# ANA_FE.net
KiCad netlist of a schematic drawn in Altium Designer
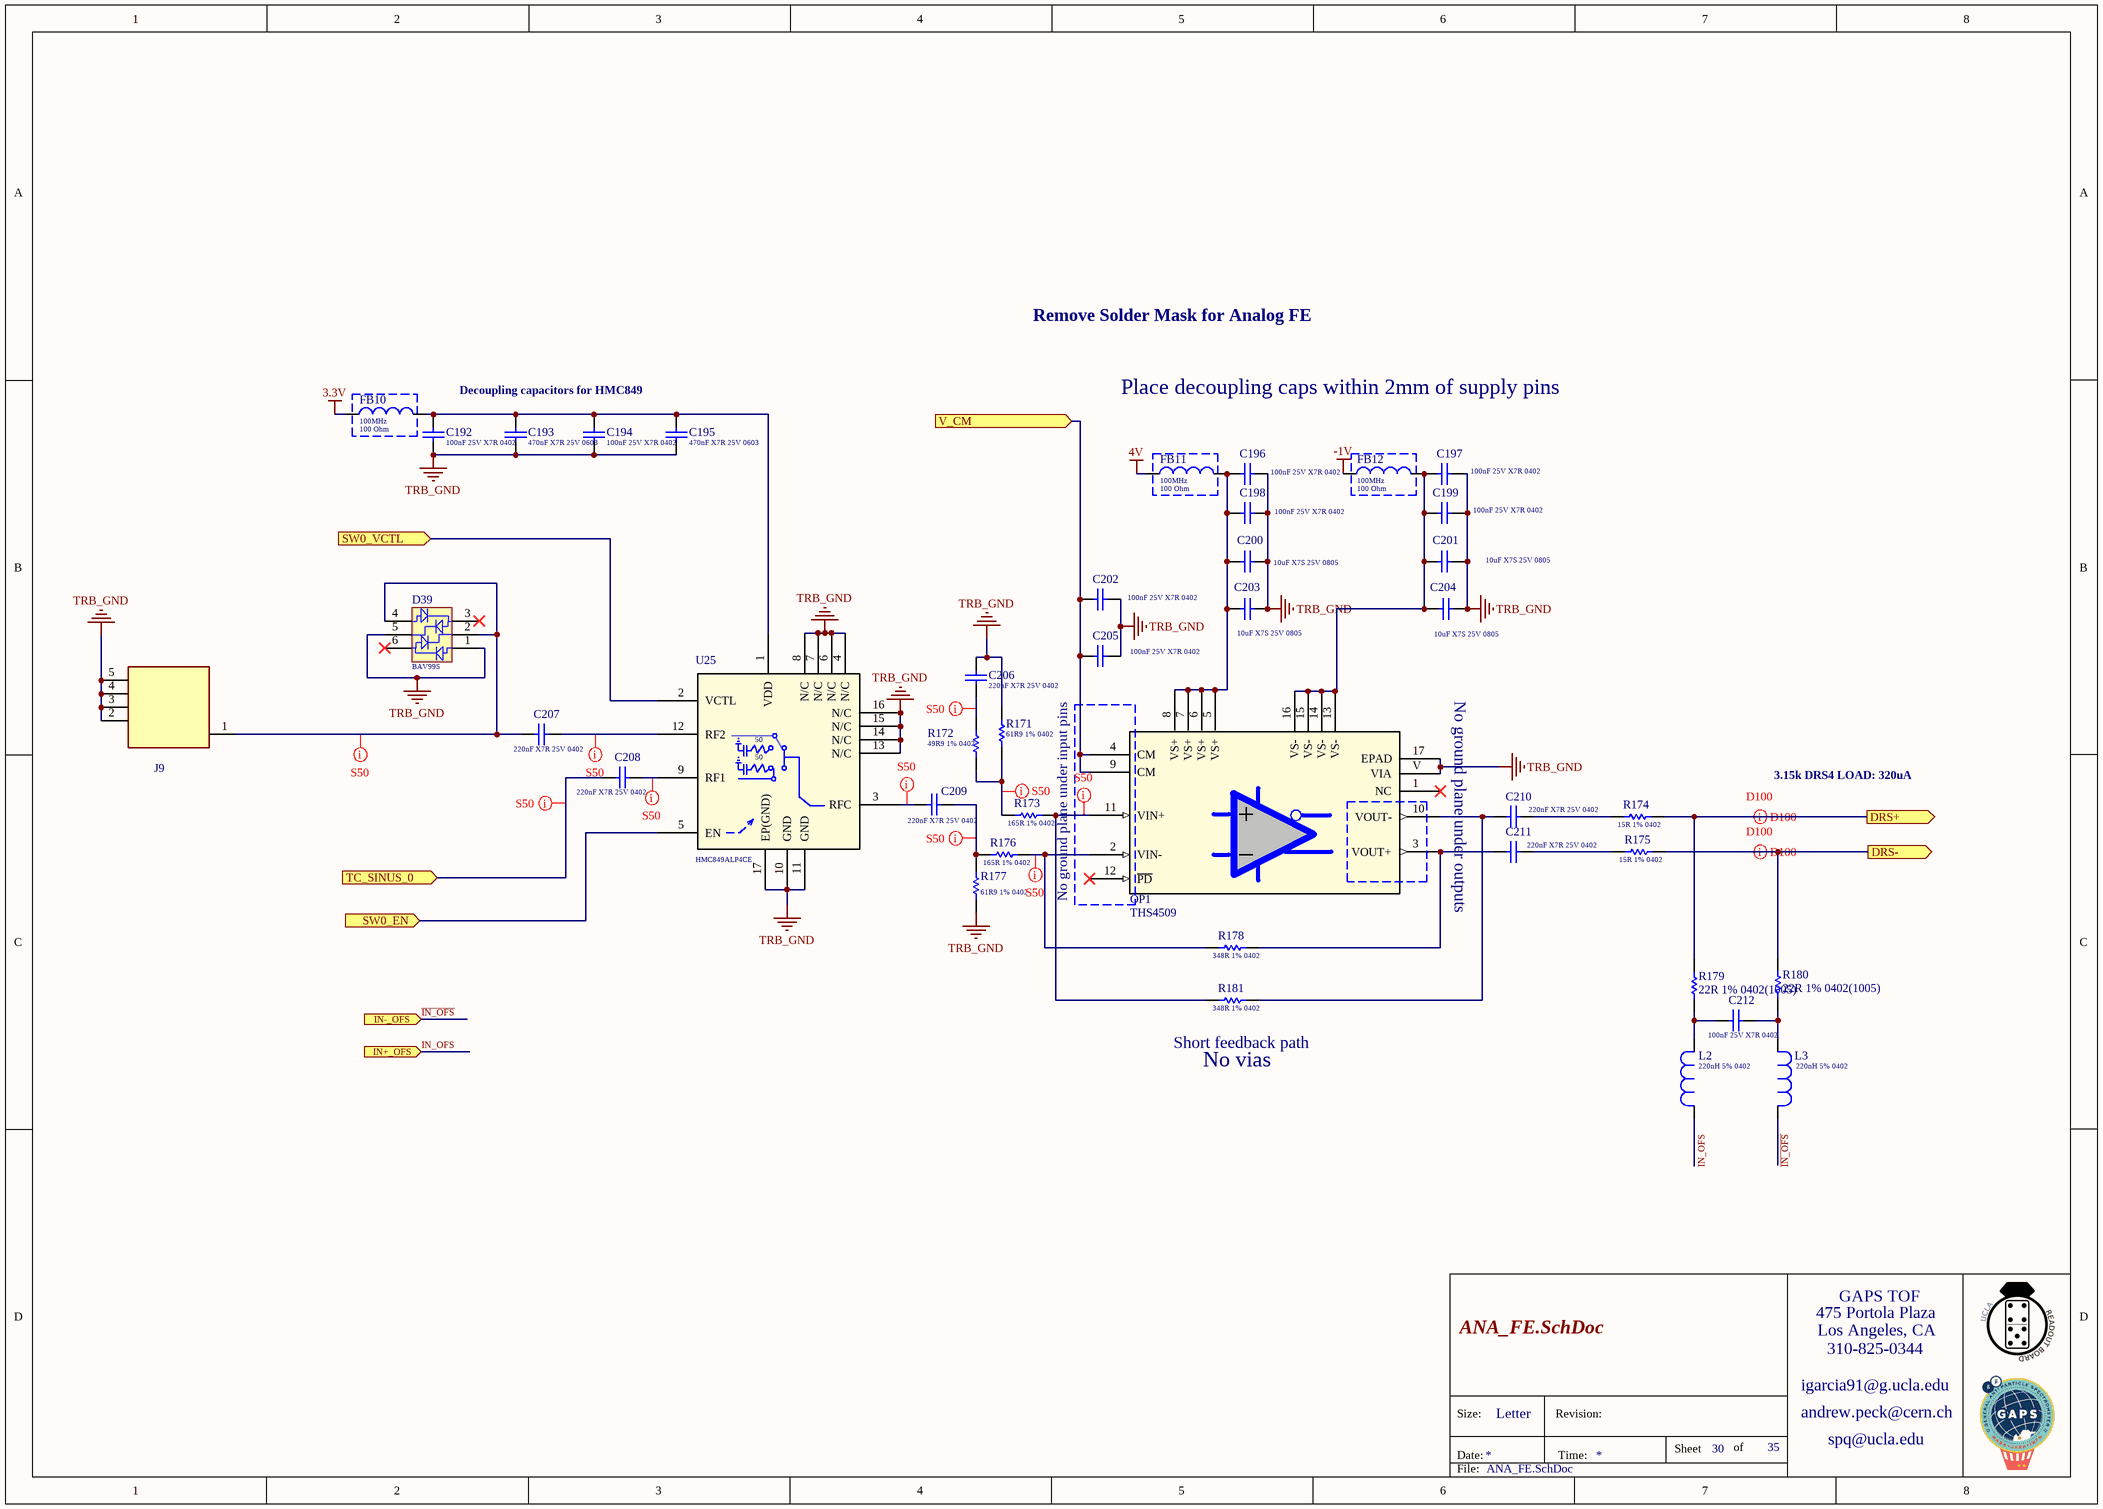
[diagram p0: ANA_FE.SchDoc]

(export (version "E")
  (design (tool "Eeschema 10.0.6"))
  (components
    (comp (ref "C192")
      (value "Cap_Taiyo_Yuden_TMK105B7104KV-FR_100nF")
      (footprint "Cap_Taiyo_Yuden_TMK105B7104KV-FR_100nF")
      (description "CAP CER 100nF 25V X7R 0402")
      (fields (field (name "CAPACITANCE") "100nF 25V X7R 0402"))
      (libsource (lib "Cap_Taiyo_Yuden_TMK105B7104KV-FR_100nF") (part "Cap_Taiyo_Yuden_TMK105B7104KV-FR_100nF"))
    )
    (comp (ref "C193")
      (value "Cap_Wurth_Electronics_885012206075_470nF")
      (footprint "Cap_Wurth_Electronics_885012206075_470nF")
      (description "CAP CER 470nF 25V X7R 0603")
      (fields (field (name "CAPACITANCE") "470nF X7R 25V 0603"))
      (libsource (lib "Cap_Wurth_Electronics_885012206075_470nF") (part "Cap_Wurth_Electronics_885012206075_470nF"))
    )
    (comp (ref "C194")
      (value "Cap_Taiyo_Yuden_TMK105B7104KV-FR_100nF")
      (footprint "Cap_Taiyo_Yuden_TMK105B7104KV-FR_100nF")
      (description "CAP CER 100nF 25V X7R 0402")
      (fields (field (name "CAPACITANCE") "100nF 25V X7R 0402"))
      (libsource (lib "Cap_Taiyo_Yuden_TMK105B7104KV-FR_100nF") (part "Cap_Taiyo_Yuden_TMK105B7104KV-FR_100nF"))
    )
    (comp (ref "C195")
      (value "Cap_Wurth_Electronics_885012206075_470nF")
      (footprint "Cap_Wurth_Electronics_885012206075_470nF")
      (description "CAP CER 470nF 25V X7R 0603")
      (fields (field (name "CAPACITANCE") "470nF X7R 25V 0603"))
      (libsource (lib "Cap_Wurth_Electronics_885012206075_470nF") (part "Cap_Wurth_Electronics_885012206075_470nF"))
    )
    (comp (ref "C196")
      (value "Cap_Taiyo_Yuden_TMK105B7104KV-FR_100nF")
      (footprint "Cap_Taiyo_Yuden_TMK105B7104KV-FR_100nF")
      (description "CAP CER 100nF 25V X7R 0402")
      (fields (field (name "CAPACITANCE") "100nF 25V X7R 0402"))
      (libsource (lib "Cap_Taiyo_Yuden_TMK105B7104KV-FR_100nF") (part "Cap_Taiyo_Yuden_TMK105B7104KV-FR_100nF"))
    )
    (comp (ref "C197")
      (value "Cap_Taiyo_Yuden_TMK105B7104KV-FR_100nF")
      (footprint "Cap_Taiyo_Yuden_TMK105B7104KV-FR_100nF")
      (description "CAP CER 100nF 25V X7R 0402")
      (fields (field (name "CAPACITANCE") "100nF 25V X7R 0402"))
      (libsource (lib "Cap_Taiyo_Yuden_TMK105B7104KV-FR_100nF") (part "Cap_Taiyo_Yuden_TMK105B7104KV-FR_100nF"))
    )
    (comp (ref "C198")
      (value "Cap_Taiyo_Yuden_TMK105B7104KV-FR_100nF")
      (footprint "Cap_Taiyo_Yuden_TMK105B7104KV-FR_100nF")
      (description "CAP CER 100nF 25V X7R 0402")
      (fields (field (name "CAPACITANCE") "100nF 25V X7R 0402"))
      (libsource (lib "Cap_Taiyo_Yuden_TMK105B7104KV-FR_100nF") (part "Cap_Taiyo_Yuden_TMK105B7104KV-FR_100nF"))
    )
    (comp (ref "C199")
      (value "Cap_Taiyo_Yuden_TMK105B7104KV-FR_100nF")
      (footprint "Cap_Taiyo_Yuden_TMK105B7104KV-FR_100nF")
      (description "CAP CER 100nF 25V X7R 0402")
      (fields (field (name "CAPACITANCE") "100nF 25V X7R 0402"))
      (libsource (lib "Cap_Taiyo_Yuden_TMK105B7104KV-FR_100nF") (part "Cap_Taiyo_Yuden_TMK105B7104KV-FR_100nF"))
    )
    (comp (ref "C200")
      (value "Cap_Murata_ GRM21BC71E106ME11L_10uF")
      (footprint "Cap_Murata_ GRM21BC71E106ME11L_10uF")
      (description "CAP CER 10uF 25V X7R 0805")
      (fields (field (name "CAPACITANCE") "10uF X7S 25V 0805"))
      (libsource (lib "Cap_Murata_ GRM21BC71E106ME11L_10uF") (part "Cap_Murata_ GRM21BC71E106ME11L_10uF"))
    )
    (comp (ref "C201")
      (value "Cap_Murata_ GRM21BC71E106ME11L_10uF")
      (footprint "Cap_Murata_ GRM21BC71E106ME11L_10uF")
      (description "CAP CER 10uF 25V X7R 0805")
      (fields (field (name "CAPACITANCE") "10uF X7S 25V 0805"))
      (libsource (lib "Cap_Murata_ GRM21BC71E106ME11L_10uF") (part "Cap_Murata_ GRM21BC71E106ME11L_10uF"))
    )
    (comp (ref "C202")
      (value "Cap_Taiyo_Yuden_TMK105B7104KV-FR_100nF")
      (footprint "Cap_Taiyo_Yuden_TMK105B7104KV-FR_100nF")
      (description "CAP CER 100nF 25V X7R 0402")
      (fields (field (name "CAPACITANCE") "100nF 25V X7R 0402"))
      (libsource (lib "Cap_Taiyo_Yuden_TMK105B7104KV-FR_100nF") (part "Cap_Taiyo_Yuden_TMK105B7104KV-FR_100nF"))
    )
    (comp (ref "C203")
      (value "Cap_Murata_ GRM21BC71E106ME11L_10uF")
      (footprint "Cap_Murata_ GRM21BC71E106ME11L_10uF")
      (description "CAP CER 10uF 25V X7R 0805")
      (fields (field (name "CAPACITANCE") "10uF X7S 25V 0805"))
      (libsource (lib "Cap_Murata_ GRM21BC71E106ME11L_10uF") (part "Cap_Murata_ GRM21BC71E106ME11L_10uF"))
    )
    (comp (ref "C204")
      (value "Cap_Murata_ GRM21BC71E106ME11L_10uF")
      (footprint "Cap_Murata_ GRM21BC71E106ME11L_10uF")
      (description "CAP CER 10uF 25V X7R 0805")
      (fields (field (name "CAPACITANCE") "10uF X7S 25V 0805"))
      (libsource (lib "Cap_Murata_ GRM21BC71E106ME11L_10uF") (part "Cap_Murata_ GRM21BC71E106ME11L_10uF"))
    )
    (comp (ref "C205")
      (value "Cap_Taiyo_Yuden_TMK105B7104KV-FR_100nF")
      (footprint "Cap_Taiyo_Yuden_TMK105B7104KV-FR_100nF")
      (description "CAP CER 100nF 25V X7R 0402")
      (fields (field (name "CAPACITANCE") "100nF 25V X7R 0402"))
      (libsource (lib "Cap_Taiyo_Yuden_TMK105B7104KV-FR_100nF") (part "Cap_Taiyo_Yuden_TMK105B7104KV-FR_100nF"))
    )
    (comp (ref "C206")
      (value "Cap_TDK_C1608X5R1A106M080AC_220nF")
      (footprint "Cap_TDK_C1608X5R1A106M080AC_220nF")
      (description "CAP CER 220nF 50V X7R 0402")
      (fields (field (name "CAPACITANCE") "220nF X7R 25V 0402"))
      (libsource (lib "Cap_TDK_C1608X5R1A106M080AC_220nF") (part "Cap_TDK_C1608X5R1A106M080AC_220nF"))
    )
    (comp (ref "C207")
      (value "Cap_TDK_C1608X5R1A106M080AC_220nF")
      (footprint "Cap_TDK_C1608X5R1A106M080AC_220nF")
      (description "CAP CER 220nF 50V X7R 0402")
      (fields (field (name "CAPACITANCE") "220nF X7R 25V 0402"))
      (libsource (lib "Cap_TDK_C1608X5R1A106M080AC_220nF") (part "Cap_TDK_C1608X5R1A106M080AC_220nF"))
    )
    (comp (ref "C208")
      (value "Cap_TDK_C1608X5R1A106M080AC_220nF")
      (footprint "Cap_TDK_C1608X5R1A106M080AC_220nF")
      (description "CAP CER 220nF 50V X7R 0402")
      (fields (field (name "CAPACITANCE") "220nF X7R 25V 0402"))
      (libsource (lib "Cap_TDK_C1608X5R1A106M080AC_220nF") (part "Cap_TDK_C1608X5R1A106M080AC_220nF"))
    )
    (comp (ref "C209")
      (value "Cap_TDK_C1608X5R1A106M080AC_220nF")
      (footprint "Cap_TDK_C1608X5R1A106M080AC_220nF")
      (description "CAP CER 220nF 50V X7R 0402")
      (fields (field (name "CAPACITANCE") "220nF X7R 25V 0402"))
      (libsource (lib "Cap_TDK_C1608X5R1A106M080AC_220nF") (part "Cap_TDK_C1608X5R1A106M080AC_220nF"))
    )
    (comp (ref "C210")
      (value "Cap_TDK_C1608X5R1A106M080AC_220nF")
      (footprint "Cap_TDK_C1608X5R1A106M080AC_220nF")
      (description "CAP CER 220nF 50V X7R 0402")
      (fields (field (name "CAPACITANCE") "220nF X7R 25V 0402"))
      (libsource (lib "Cap_TDK_C1608X5R1A106M080AC_220nF") (part "Cap_TDK_C1608X5R1A106M080AC_220nF"))
    )
    (comp (ref "C211")
      (value "Cap_TDK_C1608X5R1A106M080AC_220nF")
      (footprint "Cap_TDK_C1608X5R1A106M080AC_220nF")
      (description "CAP CER 220nF 50V X7R 0402")
      (fields (field (name "CAPACITANCE") "220nF X7R 25V 0402"))
      (libsource (lib "Cap_TDK_C1608X5R1A106M080AC_220nF") (part "Cap_TDK_C1608X5R1A106M080AC_220nF"))
    )
    (comp (ref "C212")
      (value "Cap_Taiyo_Yuden_TMK105B7104KV-FR_100nF")
      (footprint "Cap_Taiyo_Yuden_TMK105B7104KV-FR_100nF")
      (description "CAP CER 100nF 25V X7R 0402")
      (fields (field (name "CAPACITANCE") "100nF 25V X7R 0402"))
      (libsource (lib "Cap_Taiyo_Yuden_TMK105B7104KV-FR_100nF") (part "Cap_Taiyo_Yuden_TMK105B7104KV-FR_100nF"))
    )
    (comp (ref "D39")
      (value "BAV99S")
      (footprint "INF-SOT363_V")
      (description "Silicon Switching Diode, SOT363, Reel, Green")
      (fields (field (name "MANUFACTURER") "Infineon"))
      (libsource (lib "Altium Content Vault") (part "INF-D_A1K2C3A4K5C6-6"))
    )
    (comp (ref "FB10")
      (value "742792731")
      (footprint "FB_Wurth_Electronics_742792731_100Ohms")
      (description "FB SMD 100 OHM 25% 1.2A 0402")
      (fields (field (name "MEASURING FREQUENCY") "100MHz") (field (name "IMPEDANCE") "100 Ohm"))
      (libsource (lib "FB_Wurth_Electronics_742792731_100Ohms") (part "FB_Wurth_Electronics_742792731_100Ohms"))
    )
    (comp (ref "FB11")
      (value "742792731")
      (footprint "FB_Wurth_Electronics_742792731_100Ohms")
      (description "FB SMD 100 OHM 25% 1.2A 0402")
      (fields (field (name "MEASURING FREQUENCY") "100MHz") (field (name "IMPEDANCE") "100 Ohm"))
      (libsource (lib "FB_Wurth_Electronics_742792731_100Ohms") (part "FB_Wurth_Electronics_742792731_100Ohms"))
    )
    (comp (ref "FB12")
      (value "742792731")
      (footprint "FB_Wurth_Electronics_742792731_100Ohms")
      (description "FB SMD 100 OHM 25% 1.2A 0402")
      (fields (field (name "MEASURING FREQUENCY") "100MHz") (field (name "IMPEDANCE") "100 Ohm"))
      (libsource (lib "FB_Wurth_Electronics_742792731_100Ohms") (part "FB_Wurth_Electronics_742792731_100Ohms"))
    )
    (comp (ref "J9")
      (value "SMA JACK 50 OHM")
      (footprint "Amphenol_132289_0")
      (description "CONN SMA JACK 50 OHM EDGE MNT")
      (fields (field (name "MANUFACTURER") "Amphenol") (field (name "MOUSER PART NUMBER") "523-132289"))
      (libsource (lib "Conn_Amphenol_132289_eec") (part "Conn_Amphenol_132289_eec"))
    )
    (comp (ref "L2")
      (value "Ind_TDK_ MLG1005SR22JT000_220nH")
      (footprint "Ind_TDK_ MLG1005SR22JT000_220nH")
      (description "Fixed Inductors .22 UH 5%")
      (fields (field (name "INDUCTANCE") "220nH 5% 0402"))
      (libsource (lib "Ind_TDK_ MLG1005SR22JT000_220nH") (part "Ind_TDK_ MLG1005SR22JT000_220nH"))
    )
    (comp (ref "L3")
      (value "Ind_TDK_ MLG1005SR22JT000_220nH")
      (footprint "Ind_TDK_ MLG1005SR22JT000_220nH")
      (description "Fixed Inductors .22 UH 5%")
      (fields (field (name "INDUCTANCE") "220nH 5% 0402"))
      (libsource (lib "Ind_TDK_ MLG1005SR22JT000_220nH") (part "Ind_TDK_ MLG1005SR22JT000_220nH"))
    )
    (comp (ref "OP1")
      (value "THS4509")
      (footprint "RGT16")
      (description "Differential Amplifier 1 Circuit Differential 16-QFN (3x3)")
      (fields (field (name "MANUFACTURER_PART_NUMBER") "THS4509RGTT"))
      (libsource (lib "THS4509RGTT") (part "THS4509RGTT"))
    )
    (comp (ref "R171")
      (value "61R9 1% 0402")
      (footprint "RESC0402(1005)_L")
      (description "61R9 0.063W 1% 0402 (1005 Metric)  SMD")
      (fields (field (name "TOLERANCE") "1 %") (field (name "POWER") "0.063 W"))
      (libsource (lib "Altium Content Vault") (part "RES"))
    )
    (comp (ref "R172")
      (value "49R9 1% 0402")
      (footprint "RESC0402(1005)_L")
      (description "49R9 0.063W 1% 0402 (1005 Metric)  SMD")
      (fields (field (name "POWER") "0.063 W") (field (name "TOLERANCE") "1 %"))
      (libsource (lib "Altium Content Vault") (part "RES"))
    )
    (comp (ref "R173")
      (value "165R 1% 0402")
      (footprint "RESC0402(1005)_L")
      (description "165R 0.063W 1% 0402 (1005 Metric)  SMD")
      (fields (field (name "POWER") "0.063 W") (field (name "TOLERANCE") "1 %"))
      (libsource (lib "Altium Content Vault") (part "RES"))
    )
    (comp (ref "R174")
      (value "15R 1% 0402")
      (footprint "RESC0402(1005)_L")
      (description "15R 0.063W 1% 0402 (1005 Metric)  SMD")
      (fields (field (name "TOLERANCE") "1 %") (field (name "POWER") "0.063 W"))
      (libsource (lib "Altium Content Vault") (part "RES"))
    )
    (comp (ref "R175")
      (value "15R 1% 0402")
      (footprint "RESC0402(1005)_L")
      (description "15R 0.063W 1% 0402 (1005 Metric)  SMD")
      (fields (field (name "TOLERANCE") "1 %") (field (name "POWER") "0.063 W"))
      (libsource (lib "Altium Content Vault") (part "RES"))
    )
    (comp (ref "R176")
      (value "165R 1% 0402")
      (footprint "RESC0402(1005)_L")
      (description "165R 0.063W 1% 0402 (1005 Metric)  SMD")
      (fields (field (name "POWER") "0.063 W") (field (name "TOLERANCE") "1 %"))
      (libsource (lib "Altium Content Vault") (part "RES"))
    )
    (comp (ref "R177")
      (value "61R9 1% 0402")
      (footprint "RESC0402(1005)_L")
      (description "61R9 0.063W 1% 0402 (1005 Metric)  SMD")
      (fields (field (name "TOLERANCE") "1 %") (field (name "POWER") "0.063 W"))
      (libsource (lib "Altium Content Vault") (part "RES"))
    )
    (comp (ref "R178")
      (value "348R 1% 0402")
      (footprint "RESC0402(1005)_L")
      (description "348R 0.063W 1% 0402 (1005 Metric)  SMD")
      (fields (field (name "TOLERANCE") "1 %") (field (name "POWER") "0.063 W"))
      (libsource (lib "Altium Content Vault") (part "RES"))
    )
    (comp (ref "R179")
      (value "22R 1% 0402(1005)")
      (footprint "RESC0402(1005)_N")
      (description "22R 0.063W 1% 0402 (1005 Metric)  SMD")
      (fields (field (name "TOLERANCE") "1 %") (field (name "POWER") "0.063 W"))
      (libsource (lib "Altium Content Vault") (part "RES"))
    )
    (comp (ref "R180")
      (value "22R 1% 0402(1005)")
      (footprint "RESC0402(1005)_N")
      (description "22R 0.063W 1% 0402 (1005 Metric)  SMD")
      (fields (field (name "TOLERANCE") "1 %") (field (name "POWER") "0.063 W"))
      (libsource (lib "Altium Content Vault") (part "RES"))
    )
    (comp (ref "R181")
      (value "348R 1% 0402")
      (footprint "RESC0402(1005)_L")
      (description "348R 0.063W 1% 0402 (1005 Metric)  SMD")
      (fields (field (name "TOLERANCE") "1 %") (field (name "POWER") "0.063 W"))
      (libsource (lib "Altium Content Vault") (part "RES"))
    )
    (comp (ref "U25")
      (value "HMC849")
      (footprint "CP_16_40")
      (description "RF Switch ICs DC-6 GHZ Hi Isolation Switch")
      (fields (field (name "MANUFACTURER_PART_NUMBER") "HMC849ALP4CE") (field (name "SERIES") "HMC849ALP4CE"))
      (libsource (lib "HMC849ALP4CE") (part "HMC849ALP4CE"))
    )
  )
  (nets
    (net (code "1") (name "-1V") (class "Default")
      (node (ref "FB12") (pin "1") (pinfunction "1_1") (pintype "passive"))
    )
    (net (code "2") (name "/DRS+") (class "Default")
      (node (ref "R174") (pin "2") (pinfunction "2_2") (pintype "passive"))
      (node (ref "R179") (pin "2") (pinfunction "2_2") (pintype "passive"))
    )
    (net (code "3") (name "/DRS-") (class "Default")
      (node (ref "R175") (pin "2") (pinfunction "2_2") (pintype "passive"))
      (node (ref "R180") (pin "2") (pinfunction "2_2") (pintype "passive"))
    )
    (net (code "4") (name "/IN_OFS") (class "Default")
      (node (ref "L2") (pin "2") (pinfunction "2_2") (pintype "passive"))
    )
    (net (code "5") (name "/SW0_EN") (class "Default")
      (node (ref "U25") (pin "5") (pinfunction "EN_5") (pintype "passive"))
    )
    (net (code "6") (name "/SW0_VCTL") (class "Default")
      (node (ref "U25") (pin "2") (pinfunction "VCTL_2") (pintype "passive"))
    )
    (net (code "7") (name "/TC_SINUS_0") (class "Default")
      (node (ref "C208") (pin "2") (pinfunction "2_2") (pintype "passive"))
    )
    (net (code "8") (name "/V_CM") (class "Default")
      (node (ref "C202") (pin "1") (pinfunction "1_1") (pintype "passive"))
      (node (ref "C205") (pin "1") (pinfunction "1_1") (pintype "passive"))
      (node (ref "OP1") (pin "4") (pinfunction "CM_4") (pintype "passive"))
      (node (ref "OP1") (pin "9") (pinfunction "CM_9") (pintype "passive"))
    )
    (net (code "9") (name "/~{IN_OFS}") (class "Default")
      (node (ref "L3") (pin "1") (pinfunction "1_1") (pintype "passive"))
    )
    (net (code "10") (name "3.3V") (class "Default")
      (node (ref "FB10") (pin "1") (pinfunction "1_1") (pintype "passive"))
    )
    (net (code "11") (name "4V") (class "Default")
      (node (ref "FB11") (pin "1") (pinfunction "1_1") (pintype "passive"))
    )
    (net (code "12") (name "Net-(C196-Pad1)") (class "Default")
      (node (ref "C196") (pin "1") (pinfunction "1_1") (pintype "passive"))
      (node (ref "C198") (pin "1") (pinfunction "1_1") (pintype "passive"))
      (node (ref "C200") (pin "2") (pinfunction "2_2") (pintype "passive"))
      (node (ref "C203") (pin "2") (pinfunction "2_2") (pintype "passive"))
      (node (ref "FB11") (pin "2") (pinfunction "2_2") (pintype "passive"))
      (node (ref "OP1") (pin "5") (pinfunction "VS+_5") (pintype "power_in"))
      (node (ref "OP1") (pin "6") (pinfunction "VS+_6") (pintype "power_in"))
      (node (ref "OP1") (pin "7") (pinfunction "VS+_7") (pintype "power_in"))
      (node (ref "OP1") (pin "8") (pinfunction "VS+_8") (pintype "power_in"))
    )
    (net (code "13") (name "Net-(C197-Pad1)") (class "Default")
      (node (ref "C197") (pin "1") (pinfunction "1_1") (pintype "passive"))
      (node (ref "C199") (pin "1") (pinfunction "1_1") (pintype "passive"))
      (node (ref "C201") (pin "2") (pinfunction "2_2") (pintype "passive"))
      (node (ref "C204") (pin "2") (pinfunction "2_2") (pintype "passive"))
      (node (ref "FB12") (pin "2") (pinfunction "2_2") (pintype "passive"))
      (node (ref "OP1") (pin "13") (pinfunction "VS-_13") (pintype "power_in"))
      (node (ref "OP1") (pin "14") (pinfunction "VS-_14") (pintype "power_in"))
      (node (ref "OP1") (pin "15") (pinfunction "VS-_15") (pintype "power_in"))
      (node (ref "OP1") (pin "16") (pinfunction "VS-_16") (pintype "power_in"))
    )
    (net (code "14") (name "Net-(C206-Pad2)") (class "Default")
      (node (ref "C206") (pin "2") (pinfunction "2_2") (pintype "passive"))
      (node (ref "R172") (pin "2") (pinfunction "2_2") (pintype "passive"))
    )
    (net (code "15") (name "Net-(C209-Pad1)") (class "Default")
      (node (ref "C209") (pin "1") (pinfunction "1_1") (pintype "passive"))
      (node (ref "R176") (pin "1") (pinfunction "1_1") (pintype "passive"))
      (node (ref "R177") (pin "2") (pinfunction "2_2") (pintype "passive"))
    )
    (net (code "16") (name "Net-(C210-Pad1)") (class "Default")
      (node (ref "C210") (pin "1") (pinfunction "1_1") (pintype "passive"))
      (node (ref "R174") (pin "1") (pinfunction "1_1") (pintype "passive"))
    )
    (net (code "17") (name "Net-(C211-Pad1)") (class "Default")
      (node (ref "C211") (pin "1") (pinfunction "1_1") (pintype "passive"))
      (node (ref "R175") (pin "1") (pinfunction "1_1") (pintype "passive"))
    )
    (net (code "18") (name "Net-(C212-Pad1)") (class "Default")
      (node (ref "C212") (pin "1") (pinfunction "1_1") (pintype "passive"))
      (node (ref "L2") (pin "1") (pinfunction "1_1") (pintype "passive"))
      (node (ref "R179") (pin "1") (pinfunction "1_1") (pintype "passive"))
    )
    (net (code "19") (name "Net-(C212-Pad2)") (class "Default")
      (node (ref "C212") (pin "2") (pinfunction "2_2") (pintype "passive"))
      (node (ref "L3") (pin "2") (pinfunction "2_2") (pintype "passive"))
      (node (ref "R180") (pin "1") (pinfunction "1_1") (pintype "passive"))
    )
    (net (code "20") (name "Net-(D39-A4)") (class "Default")
      (node (ref "C207") (pin "2") (pinfunction "2_2") (pintype "passive"))
      (node (ref "D39") (pin "2") (pinfunction "K2_2") (pintype "passive"))
      (node (ref "D39") (pin "4") (pinfunction "A4_4") (pintype "passive"))
      (node (ref "J9") (pin "1") (pinfunction "1_1") (pintype "passive"))
    )
    (net (code "21") (name "Net-(OP1-VIN+)") (class "Default")
      (node (ref "OP1") (pin "11") (pinfunction "VIN+_11") (pintype "input"))
      (node (ref "R173") (pin "2") (pinfunction "2_2") (pintype "passive"))
      (node (ref "R181") (pin "1") (pinfunction "1_1") (pintype "passive"))
    )
    (net (code "22") (name "Net-(OP1-VIN-)") (class "Default")
      (node (ref "OP1") (pin "2") (pinfunction "VIN-_2") (pintype "input"))
      (node (ref "R176") (pin "2") (pinfunction "2_2") (pintype "passive"))
      (node (ref "R178") (pin "1") (pinfunction "1_1") (pintype "passive"))
    )
    (net (code "23") (name "Net-(OP1-VOUT+)") (class "Default")
      (node (ref "C211") (pin "2") (pinfunction "2_2") (pintype "passive"))
      (node (ref "OP1") (pin "3") (pinfunction "VOUT+_3") (pintype "output"))
      (node (ref "R178") (pin "2") (pinfunction "2_2") (pintype "passive"))
    )
    (net (code "24") (name "Net-(OP1-VOUT-)") (class "Default")
      (node (ref "C210") (pin "2") (pinfunction "2_2") (pintype "passive"))
      (node (ref "OP1") (pin "10") (pinfunction "VOUT-_10") (pintype "output"))
      (node (ref "R181") (pin "2") (pinfunction "2_2") (pintype "passive"))
    )
    (net (code "25") (name "Net-(R171-Pad1)") (class "Default")
      (node (ref "R171") (pin "1") (pinfunction "1_1") (pintype "passive"))
      (node (ref "R172") (pin "1") (pinfunction "1_1") (pintype "passive"))
      (node (ref "R173") (pin "1") (pinfunction "1_1") (pintype "passive"))
    )
    (net (code "26") (name "Net-(U25-RF1)") (class "Default")
      (node (ref "C208") (pin "1") (pinfunction "1_1") (pintype "passive"))
      (node (ref "U25") (pin "9") (pinfunction "RF1_9") (pintype "passive"))
    )
    (net (code "27") (name "Net-(U25-RF2)") (class "Default")
      (node (ref "C207") (pin "1") (pinfunction "1_1") (pintype "passive"))
      (node (ref "U25") (pin "12") (pinfunction "RF2_12") (pintype "passive"))
    )
    (net (code "28") (name "Net-(U25-RFC)") (class "Default")
      (node (ref "C209") (pin "2") (pinfunction "2_2") (pintype "passive"))
      (node (ref "U25") (pin "3") (pinfunction "RFC_3") (pintype "passive"))
    )
    (net (code "29") (name "Net-(U25-VDD)") (class "Default")
      (node (ref "C192") (pin "2") (pinfunction "2_2") (pintype "passive"))
      (node (ref "C193") (pin "1") (pinfunction "1_1") (pintype "passive"))
      (node (ref "C194") (pin "2") (pinfunction "2_2") (pintype "passive"))
      (node (ref "C195") (pin "1") (pinfunction "1_1") (pintype "passive"))
      (node (ref "FB10") (pin "2") (pinfunction "2_2") (pintype "passive"))
      (node (ref "U25") (pin "1") (pinfunction "VDD_1") (pintype "passive"))
    )
    (net (code "30") (name "TRB_GND") (class "Default")
      (node (ref "C192") (pin "1") (pinfunction "1_1") (pintype "passive"))
      (node (ref "C193") (pin "2") (pinfunction "2_2") (pintype "passive"))
      (node (ref "C194") (pin "1") (pinfunction "1_1") (pintype "passive"))
      (node (ref "C195") (pin "2") (pinfunction "2_2") (pintype "passive"))
      (node (ref "C196") (pin "2") (pinfunction "2_2") (pintype "passive"))
      (node (ref "C197") (pin "2") (pinfunction "2_2") (pintype "passive"))
      (node (ref "C198") (pin "2") (pinfunction "2_2") (pintype "passive"))
      (node (ref "C199") (pin "2") (pinfunction "2_2") (pintype "passive"))
      (node (ref "C200") (pin "1") (pinfunction "1_1") (pintype "passive"))
      (node (ref "C201") (pin "1") (pinfunction "1_1") (pintype "passive"))
      (node (ref "C202") (pin "2") (pinfunction "2_2") (pintype "passive"))
      (node (ref "C203") (pin "1") (pinfunction "1_1") (pintype "passive"))
      (node (ref "C204") (pin "1") (pinfunction "1_1") (pintype "passive"))
      (node (ref "C205") (pin "2") (pinfunction "2_2") (pintype "passive"))
      (node (ref "C206") (pin "1") (pinfunction "1_1") (pintype "passive"))
      (node (ref "D39") (pin "1") (pinfunction "A1_1") (pintype "passive"))
      (node (ref "D39") (pin "5") (pinfunction "K5_5") (pintype "passive"))
      (node (ref "J9") (pin "2") (pinfunction "MNT_1_2") (pintype "passive"))
      (node (ref "J9") (pin "3") (pinfunction "MNT_2_3") (pintype "passive"))
      (node (ref "J9") (pin "4") (pinfunction "MNT_3_4") (pintype "passive"))
      (node (ref "J9") (pin "5") (pinfunction "MNT_4_5") (pintype "passive"))
      (node (ref "OP1") (pin "17") (pinfunction "EPAD_17") (pintype "passive"))
      (node (ref "OP1") (pin "V") (pinfunction "VIA_V") (pintype "passive"))
      (node (ref "R171") (pin "2") (pinfunction "2_2") (pintype "passive"))
      (node (ref "R177") (pin "1") (pinfunction "1_1") (pintype "passive"))
      (node (ref "U25") (pin "10") (pinfunction "GND_10") (pintype "passive"))
      (node (ref "U25") (pin "11") (pinfunction "GND_11") (pintype "passive"))
      (node (ref "U25") (pin "13") (pinfunction "N/C_13") (pintype "passive"))
      (node (ref "U25") (pin "14") (pinfunction "N/C_14") (pintype "passive"))
      (node (ref "U25") (pin "15") (pinfunction "N/C_15") (pintype "passive"))
      (node (ref "U25") (pin "16") (pinfunction "N/C_16") (pintype "passive"))
      (node (ref "U25") (pin "17") (pinfunction "EP(GND)_17") (pintype "passive"))
      (node (ref "U25") (pin "4") (pinfunction "N/C_4") (pintype "passive"))
      (node (ref "U25") (pin "6") (pinfunction "N/C_6") (pintype "passive"))
      (node (ref "U25") (pin "7") (pinfunction "N/C_7") (pintype "passive"))
      (node (ref "U25") (pin "8") (pinfunction "N/C_8") (pintype "passive"))
    )
    (net (code "31") (name "unconnected-(D39-C3-Pad3)") (class "Default")
      (node (ref "D39") (pin "3") (pinfunction "C3_3") (pintype "passive+no_connect"))
    )
    (net (code "32") (name "unconnected-(D39-C6-Pad6)") (class "Default")
      (node (ref "D39") (pin "6") (pinfunction "C6_6") (pintype "passive+no_connect"))
    )
    (net (code "33") (name "unconnected-(OP1-NC-Pad1)") (class "Default")
      (node (ref "OP1") (pin "1") (pinfunction "NC_1") (pintype "passive+no_connect"))
    )
    (net (code "34") (name "unconnected-(OP1-~{PD}-Pad12)") (class "Default")
      (node (ref "OP1") (pin "12") (pinfunction "~{PD}_12") (pintype "input+no_connect"))
    )
  )
)
